# Carte_relais_TP1.net
KiCad netlist of a schematic drawn in EAGLE
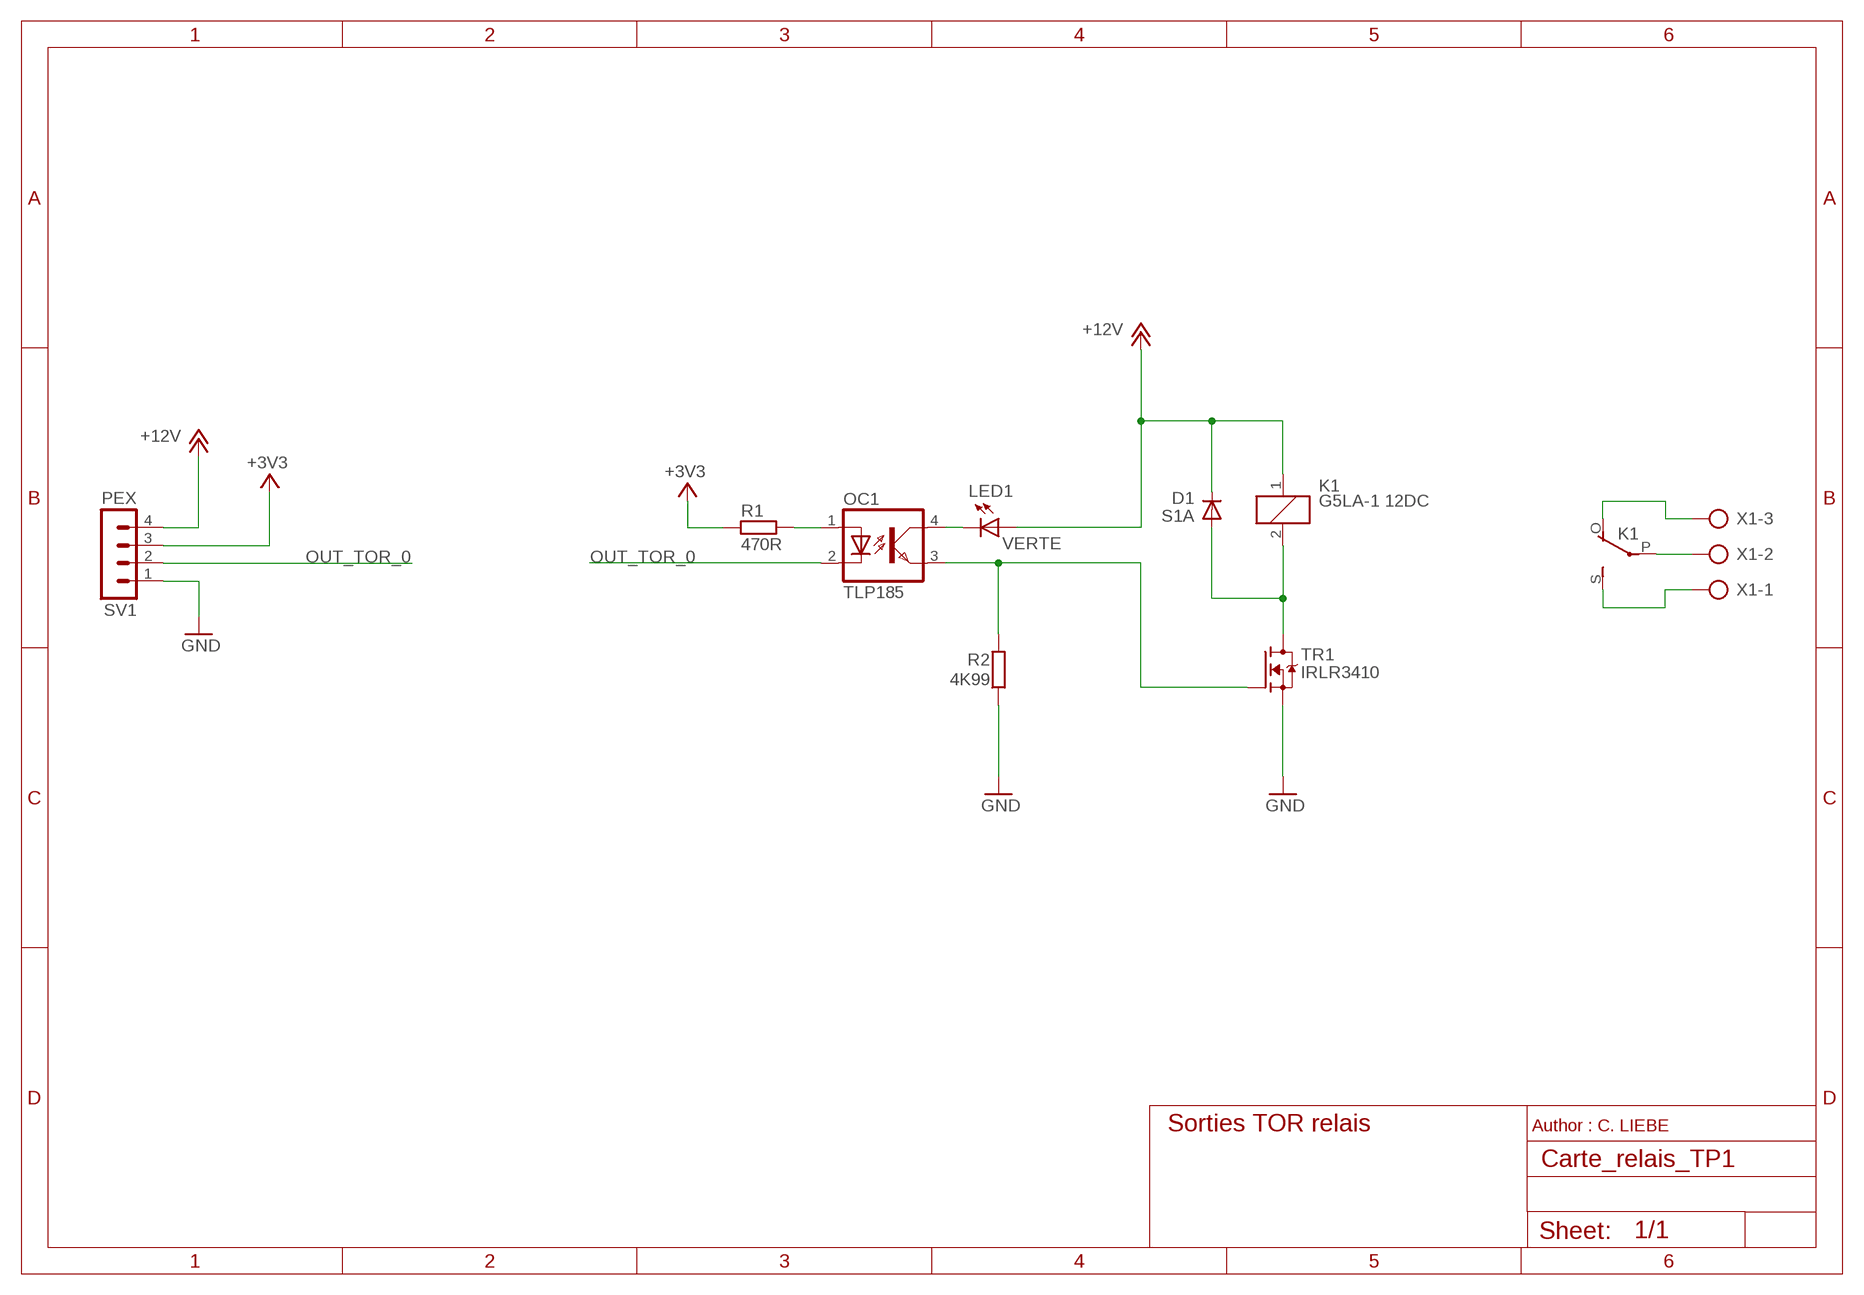
[diagram p0: schematic, sheet 1]

(export (version "E")
  (design (tool "Eeschema 10.0.6"))
  (components
    (comp (ref "D1")
      (value "S1A")
      (footprint "eagle-import:SMA-DO214AC")
      (libsource (lib "eagle-import") (part "GF1"))
    )
    (comp (ref "K1")
      (value "G5LA-1 12DC")
      (footprint "eagle-import:G5LE")
      (libsource (lib "eagle-import") (part "G5L"))
    )
    (comp (ref "LED1")
      (value "VERTE")
      (footprint "eagle-import:1206")
      (libsource (lib "eagle-import") (part "LEDSMT1206"))
    )
    (comp (ref "OC1")
      (value "TLP185")
      (footprint "eagle-import:SO-4")
      (libsource (lib "eagle-import") (part "TLP181"))
    )
    (comp (ref "R1")
      (value "470R")
      (footprint "eagle-import:R1206")
      (libsource (lib "eagle-import") (part "R-EU_R1206"))
    )
    (comp (ref "R2")
      (value "4K99")
      (footprint "eagle-import:R1206")
      (libsource (lib "eagle-import") (part "R-EU_R1206"))
    )
    (comp (ref "SV1")
      (value "PEX")
      (footprint "eagle-import:MA04-1")
      (libsource (lib "eagle-import") (part "MA04-1"))
    )
    (comp (ref "TR1")
      (value "IRLR3410")
      (footprint "eagle-import:TO252")
      (libsource (lib "eagle-import") (part "IRLR3410"))
    )
    (comp (ref "X1")
      (value "AK300/3")
      (footprint "eagle-import:AK300_3")
      (libsource (lib "eagle-import") (part "AK300/3"))
    )
  )
  (nets
    (net (code "1") (name "+3V3") (class "Default")
      (node (ref "R1") (pin "1") (pinfunction "1_1") (pintype "passive"))
      (node (ref "SV1") (pin "3") (pinfunction "3_3") (pintype "passive"))
    )
    (net (code "2") (name "+12V") (class "Default")
      (node (ref "D1") (pin "K") (pinfunction "C_K") (pintype "passive"))
      (node (ref "K1") (pin "1") (pinfunction "1_1") (pintype "passive"))
      (node (ref "LED1") (pin "A") (pinfunction "A_A") (pintype "passive"))
      (node (ref "SV1") (pin "4") (pinfunction "4_4") (pintype "passive"))
    )
    (net (code "3") (name "/OUT_TOR_0") (class "Default")
      (node (ref "OC1") (pin "2") (pinfunction "C_2") (pintype "passive"))
      (node (ref "SV1") (pin "2") (pinfunction "2_2") (pintype "passive"))
    )
    (net (code "4") (name "GND") (class "Default")
      (node (ref "R2") (pin "1") (pinfunction "1_1") (pintype "passive"))
      (node (ref "SV1") (pin "1") (pinfunction "1_1") (pintype "passive"))
      (node (ref "TR1") (pin "3") (pinfunction "S_3") (pintype "passive"))
    )
    (net (code "5") (name "Net-(OC1-A)") (class "Default")
      (node (ref "OC1") (pin "1") (pinfunction "A_1") (pintype "passive"))
      (node (ref "R1") (pin "2") (pinfunction "2_2") (pintype "passive"))
    )
    (net (code "6") (name "Net-(OC1-COL)") (class "Default")
      (node (ref "LED1") (pin "C") (pinfunction "C_C") (pintype "passive"))
      (node (ref "OC1") (pin "4") (pinfunction "COL_4") (pintype "passive"))
    )
    (net (code "7") (name "Net-(OC1-EMIT)") (class "Default")
      (node (ref "OC1") (pin "3") (pinfunction "EMIT_3") (pintype "passive"))
      (node (ref "R2") (pin "2") (pinfunction "2_2") (pintype "passive"))
      (node (ref "TR1") (pin "1") (pinfunction "G_1") (pintype "passive"))
    )
    (net (code "8") (name "Net-(TR1-D)") (class "Default")
      (node (ref "D1") (pin "A") (pinfunction "A_A") (pintype "passive"))
      (node (ref "K1") (pin "2") (pinfunction "2_2") (pintype "passive"))
      (node (ref "TR1") (pin "4") (pinfunction "D_4") (pintype "passive"))
    )
    (net (code "9") (name "Net-(X1A-KL)") (class "Default")
      (node (ref "K1") (pin "S") (pinfunction "S_S") (pintype "passive"))
      (node (ref "X1") (pin "1") (pinfunction "KL_1") (pintype "passive"))
    )
    (net (code "10") (name "Net-(X1B-KL)") (class "Default")
      (node (ref "K1") (pin "P") (pinfunction "P_P") (pintype "passive"))
      (node (ref "X1") (pin "2") (pinfunction "KL_2") (pintype "passive"))
    )
    (net (code "11") (name "Net-(X1C-KL)") (class "Default")
      (node (ref "K1") (pin "O") (pinfunction "O_O") (pintype "passive"))
      (node (ref "X1") (pin "3") (pinfunction "KL_3") (pintype "passive"))
    )
  )
)
